# at24c02_SST25FV080B_OLED.net
KiCad netlist of a schematic drawn in Altium Designer
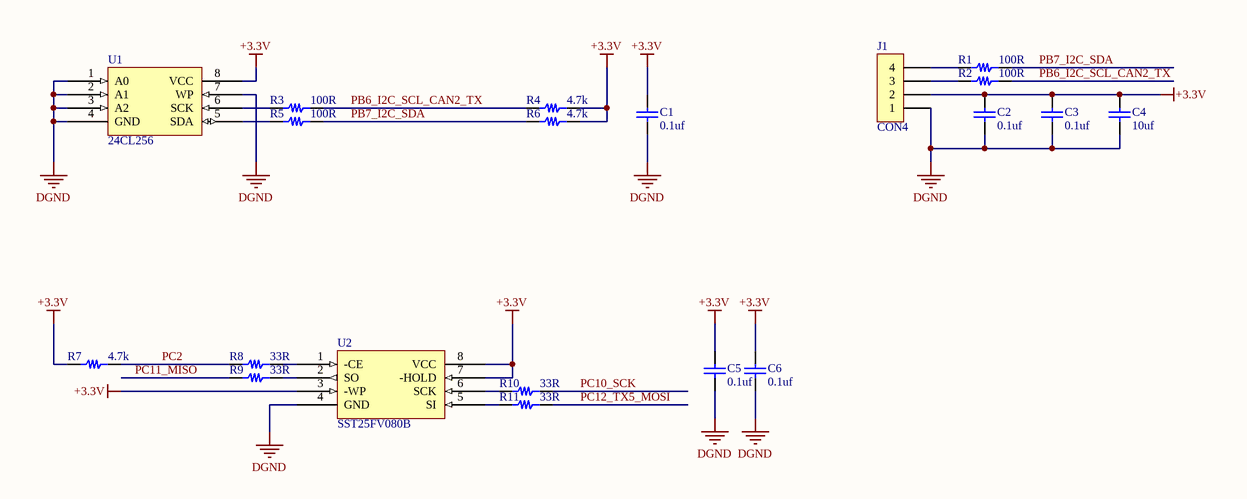
[diagram p0: at24c02_SST25FV080B_OLED.SchDoc]

(export (version "E")
  (design (tool "Eeschema 10.0.6"))
  (components
    (comp (ref "C1")
      (value "0.1uf")
      (footprint "0805C")
      (description "贴片电容")
      (fields (field (name "PUBLISHER") "Altium Limited"))
      (libsource (lib "Device_CHT") (part "Cap"))
    )
    (comp (ref "C2")
      (value "0.1uf")
      (footprint "0805C")
      (description "贴片电容")
      (fields (field (name "PUBLISHER") "Altium Limited"))
      (libsource (lib "Device_CHT") (part "Cap"))
    )
    (comp (ref "C3")
      (value "0.1uf")
      (footprint "0805C")
      (description "贴片电容")
      (fields (field (name "PUBLISHER") "Altium Limited"))
      (libsource (lib "Device_CHT") (part "Cap"))
    )
    (comp (ref "C4")
      (value "10uf")
      (footprint "0805C")
      (description "贴片电容")
      (fields (field (name "PUBLISHER") "Altium Limited"))
      (libsource (lib "Device_CHT") (part "Cap"))
    )
    (comp (ref "C5")
      (value "0.1uf")
      (footprint "0805C")
      (description "贴片电容")
      (fields (field (name "PUBLISHER") "Altium Limited"))
      (libsource (lib "Device_CHT") (part "Cap"))
    )
    (comp (ref "C6")
      (value "0.1uf")
      (footprint "0805C")
      (description "贴片电容")
      (fields (field (name "PUBLISHER") "Altium Limited"))
      (libsource (lib "Device_CHT") (part "Cap"))
    )
    (comp (ref "J1")
      (value "CON4")
      (footprint "SIP4-2.54MM")
      (description "Connector")
      (libsource (lib "Connector_Veiko") (part "CON4"))
    )
    (comp (ref "R1")
      (value "100R")
      (footprint "0805_small")
      (description "电阻")
      (fields (field (name "PUBLISHER") "Altium Limited"))
      (libsource (lib "Device_CHT") (part "Res"))
    )
    (comp (ref "R2")
      (value "100R")
      (footprint "0805_small")
      (description "电阻")
      (fields (field (name "PUBLISHER") "Altium Limited"))
      (libsource (lib "Device_CHT") (part "Res"))
    )
    (comp (ref "R3")
      (value "100R")
      (footprint "0805_small")
      (description "电阻")
      (fields (field (name "PUBLISHER") "Altium Limited"))
      (libsource (lib "Device_CHT") (part "Res"))
    )
    (comp (ref "R4")
      (value "4.7k")
      (footprint "0805_small")
      (description "电阻")
      (fields (field (name "PUBLISHER") "Altium Limited"))
      (libsource (lib "Device_CHT") (part "Res"))
    )
    (comp (ref "R5")
      (value "100R")
      (footprint "0805_small")
      (description "电阻")
      (fields (field (name "PUBLISHER") "Altium Limited"))
      (libsource (lib "Device_CHT") (part "Res"))
    )
    (comp (ref "R6")
      (value "4.7k")
      (footprint "0805_small")
      (description "电阻")
      (fields (field (name "PUBLISHER") "Altium Limited"))
      (libsource (lib "Device_CHT") (part "Res"))
    )
    (comp (ref "R7")
      (value "4.7k")
      (footprint "0805_small")
      (description "电阻")
      (fields (field (name "PUBLISHER") "Altium Limited"))
      (libsource (lib "Device_CHT") (part "Res"))
    )
    (comp (ref "R8")
      (value "33R")
      (footprint "0805_small")
      (description "电阻")
      (fields (field (name "PUBLISHER") "Altium Limited"))
      (libsource (lib "Device_CHT") (part "Res"))
    )
    (comp (ref "R9")
      (value "33R")
      (footprint "0805_small")
      (description "电阻")
      (fields (field (name "PUBLISHER") "Altium Limited"))
      (libsource (lib "Device_CHT") (part "Res"))
    )
    (comp (ref "R10")
      (value "33R")
      (footprint "0805_small")
      (description "电阻")
      (fields (field (name "PUBLISHER") "Altium Limited"))
      (libsource (lib "Device_CHT") (part "Res"))
    )
    (comp (ref "R11")
      (value "33R")
      (footprint "0805_small")
      (description "电阻")
      (fields (field (name "PUBLISHER") "Altium Limited"))
      (libsource (lib "Device_CHT") (part "Res"))
    )
    (comp (ref "U1") (value "24CL256") (footprint "SO-8") (libsource (lib "Device_CHT") (part "24CL256")))
    (comp (ref "U2")
      (value "SST25FV080B")
      (footprint "SO-8")
      (libsource (lib "Device_CHT") (part "SST25FV080B"))
    )
  )
  (nets
    (net (code "1") (name "+3.3V") (class "Default")
      (node (ref "C1") (pin "2") (pinfunction "2_2") (pintype "passive"))
      (node (ref "C2") (pin "2") (pinfunction "2_2") (pintype "passive"))
      (node (ref "C3") (pin "2") (pinfunction "2_2") (pintype "passive"))
      (node (ref "C4") (pin "2") (pinfunction "2_2") (pintype "passive"))
      (node (ref "C5") (pin "2") (pinfunction "2_2") (pintype "passive"))
      (node (ref "C6") (pin "2") (pinfunction "2_2") (pintype "passive"))
      (node (ref "J1") (pin "2") (pinfunction "2_2") (pintype "passive"))
      (node (ref "R4") (pin "1") (pinfunction "1_1") (pintype "passive"))
      (node (ref "R6") (pin "1") (pinfunction "1_1") (pintype "passive"))
      (node (ref "R7") (pin "2") (pinfunction "2_2") (pintype "passive"))
      (node (ref "U1") (pin "8") (pinfunction "VCC_8") (pintype "power_in"))
      (node (ref "U2") (pin "3") (pinfunction "-WP_3") (pintype "input"))
      (node (ref "U2") (pin "7") (pinfunction "-HOLD_7") (pintype "input"))
      (node (ref "U2") (pin "8") (pinfunction "VCC_8") (pintype "power_in"))
    )
    (net (code "2") (name "/PB6_I2C_SCL_CAN2_TX") (class "Default")
      (node (ref "R2") (pin "1") (pinfunction "1_1") (pintype "passive"))
      (node (ref "R3") (pin "1") (pinfunction "1_1") (pintype "passive"))
      (node (ref "R4") (pin "2") (pinfunction "2_2") (pintype "passive"))
    )
    (net (code "3") (name "/PB7_I2C_SDA") (class "Default")
      (node (ref "R1") (pin "1") (pinfunction "1_1") (pintype "passive"))
      (node (ref "R5") (pin "1") (pinfunction "1_1") (pintype "passive"))
      (node (ref "R6") (pin "2") (pinfunction "2_2") (pintype "passive"))
    )
    (net (code "4") (name "/PC2") (class "Default")
      (node (ref "R7") (pin "1") (pinfunction "1_1") (pintype "passive"))
      (node (ref "R8") (pin "2") (pinfunction "2_2") (pintype "passive"))
    )
    (net (code "5") (name "/PC10_SCK") (class "Default")
      (node (ref "R10") (pin "1") (pinfunction "1_1") (pintype "passive"))
    )
    (net (code "6") (name "/PC11_MISO") (class "Default")
      (node (ref "R9") (pin "2") (pinfunction "2_2") (pintype "passive"))
    )
    (net (code "7") (name "/PC12_TX5_MOSI") (class "Default")
      (node (ref "R11") (pin "1") (pinfunction "1_1") (pintype "passive"))
    )
    (net (code "8") (name "DGND") (class "Default")
      (node (ref "C1") (pin "1") (pinfunction "1_1") (pintype "passive"))
      (node (ref "C2") (pin "1") (pinfunction "1_1") (pintype "passive"))
      (node (ref "C3") (pin "1") (pinfunction "1_1") (pintype "passive"))
      (node (ref "C4") (pin "1") (pinfunction "1_1") (pintype "passive"))
      (node (ref "C5") (pin "1") (pinfunction "1_1") (pintype "passive"))
      (node (ref "C6") (pin "1") (pinfunction "1_1") (pintype "passive"))
      (node (ref "J1") (pin "1") (pinfunction "1_1") (pintype "passive"))
      (node (ref "U1") (pin "1") (pinfunction "A0_1") (pintype "input"))
      (node (ref "U1") (pin "2") (pinfunction "A1_2") (pintype "input"))
      (node (ref "U1") (pin "3") (pinfunction "A2_3") (pintype "input"))
      (node (ref "U1") (pin "4") (pinfunction "GND_4") (pintype "power_in"))
      (node (ref "U1") (pin "7") (pinfunction "WP_7") (pintype "input"))
      (node (ref "U2") (pin "4") (pinfunction "GND_4") (pintype "power_in"))
    )
    (net (code "9") (name "Net-(J1-Pad3)") (class "Default")
      (node (ref "J1") (pin "3") (pinfunction "3_3") (pintype "passive"))
      (node (ref "R2") (pin "2") (pinfunction "2_2") (pintype "passive"))
    )
    (net (code "10") (name "Net-(J1-Pad4)") (class "Default")
      (node (ref "J1") (pin "4") (pinfunction "4_4") (pintype "passive"))
      (node (ref "R1") (pin "2") (pinfunction "2_2") (pintype "passive"))
    )
    (net (code "11") (name "Net-(U1-SCK)") (class "Default")
      (node (ref "R3") (pin "2") (pinfunction "2_2") (pintype "passive"))
      (node (ref "U1") (pin "6") (pinfunction "SCK_6") (pintype "input"))
    )
    (net (code "12") (name "Net-(U1-SDA)") (class "Default")
      (node (ref "R5") (pin "2") (pinfunction "2_2") (pintype "passive"))
      (node (ref "U1") (pin "5") (pinfunction "SDA_5") (pintype "bidirectional"))
    )
    (net (code "13") (name "Net-(U2--CE)") (class "Default")
      (node (ref "R8") (pin "1") (pinfunction "1_1") (pintype "passive"))
      (node (ref "U2") (pin "1") (pinfunction "-CE_1") (pintype "input"))
    )
    (net (code "14") (name "Net-(U2-SCK)") (class "Default")
      (node (ref "R10") (pin "2") (pinfunction "2_2") (pintype "passive"))
      (node (ref "U2") (pin "6") (pinfunction "SCK_6") (pintype "input"))
    )
    (net (code "15") (name "Net-(U2-SI)") (class "Default")
      (node (ref "R11") (pin "2") (pinfunction "2_2") (pintype "passive"))
      (node (ref "U2") (pin "5") (pinfunction "SI_5") (pintype "input"))
    )
    (net (code "16") (name "Net-(U2-SO)") (class "Default")
      (node (ref "R9") (pin "1") (pinfunction "1_1") (pintype "passive"))
      (node (ref "U2") (pin "2") (pinfunction "SO_2") (pintype "output"))
    )
  )
)
